# source_eagle.net
KiCad netlist of a schematic drawn in EAGLE
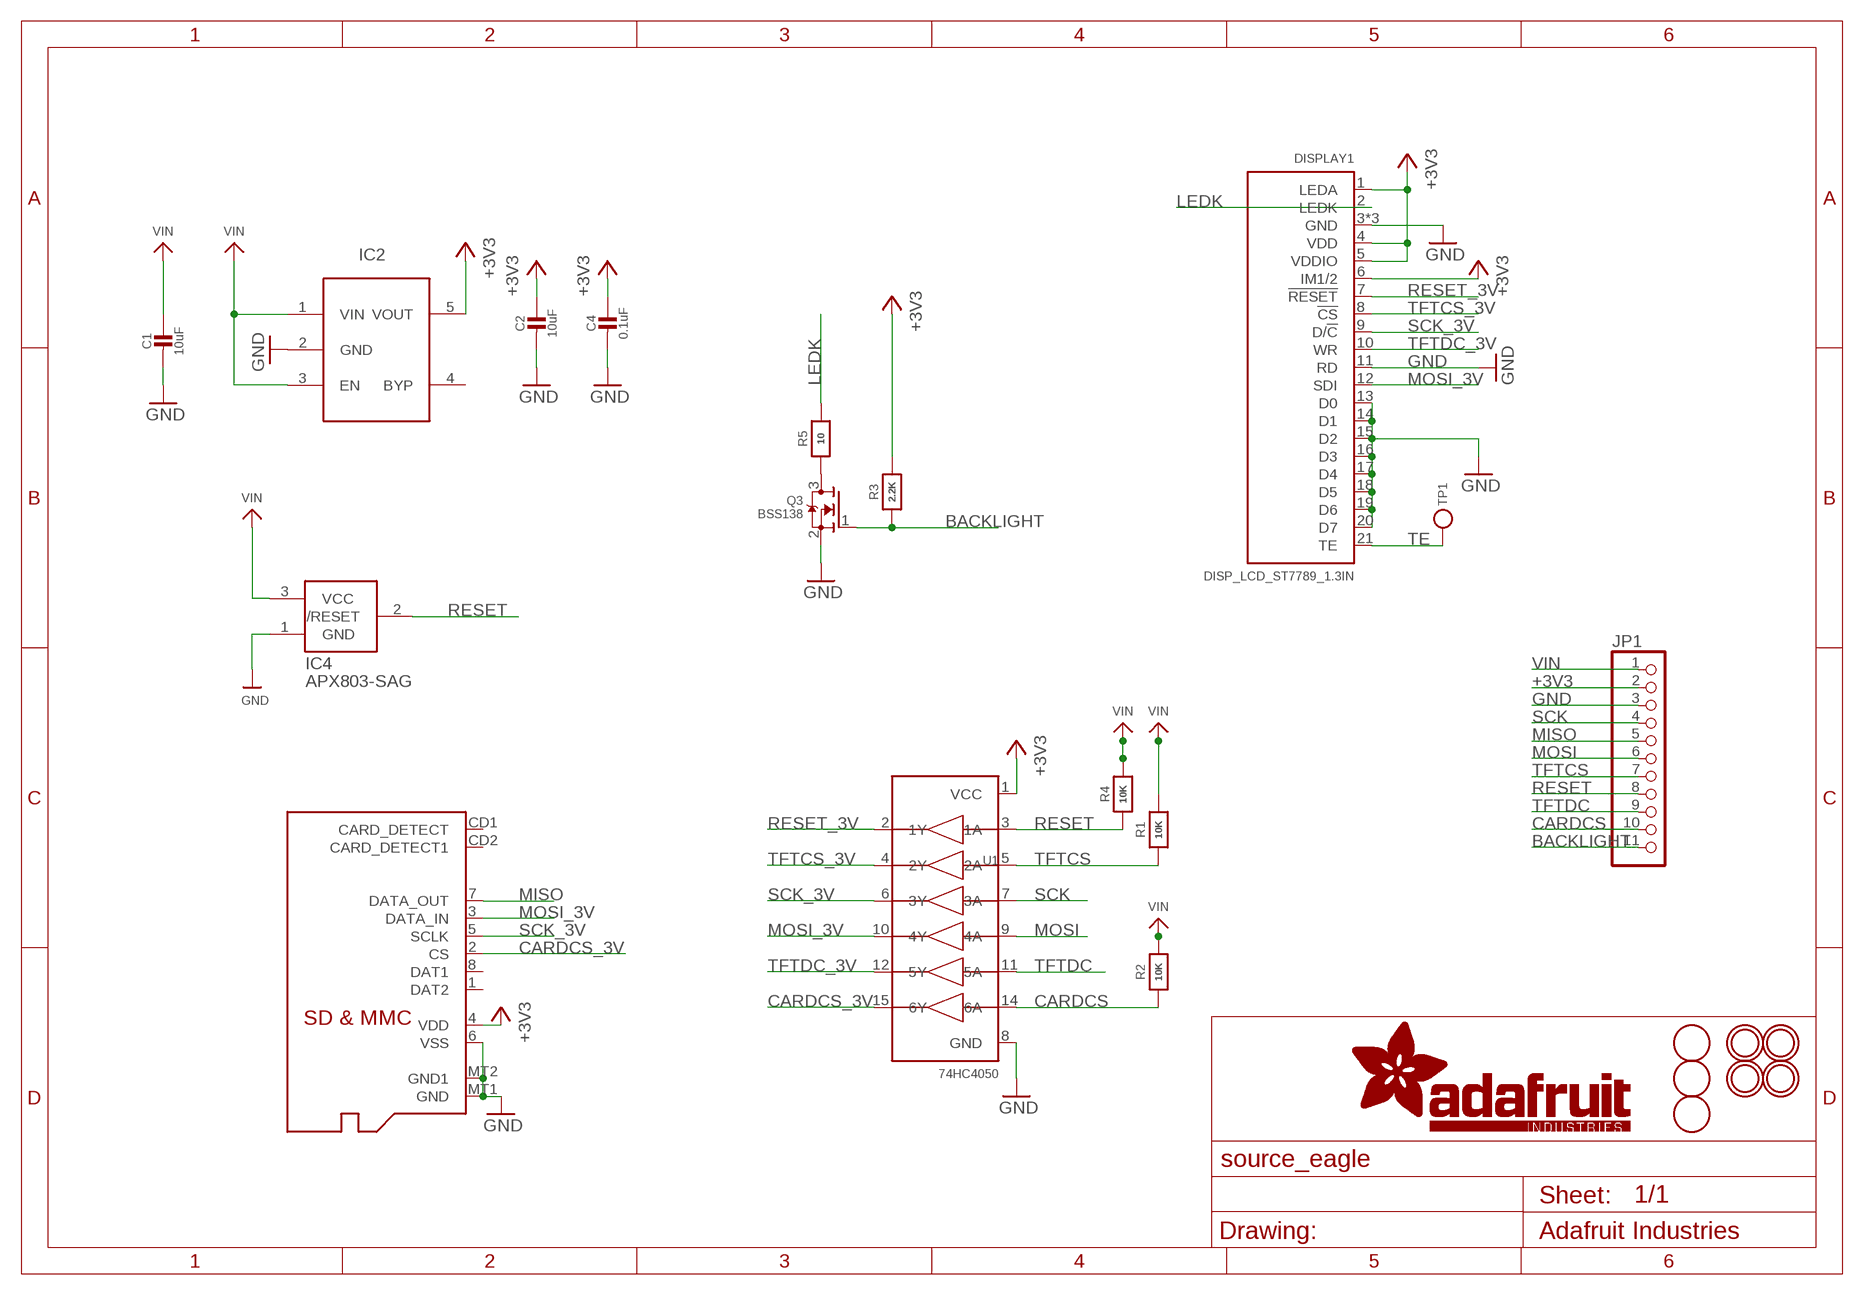
[diagram p0: schematic, sheet 1]

(export (version "E")
  (design (tool "Eeschema 10.0.6"))
  (components
    (comp (ref "C1")
      (value "10uF")
      (footprint "eagle-import:0805-NO")
      (libsource (lib "eagle-import") (part "CAP_CERAMIC0805-NOOUTLINE"))
    )
    (comp (ref "C2")
      (value "10uF")
      (footprint "eagle-import:0805-NO")
      (libsource (lib "eagle-import") (part "CAP_CERAMIC0805-NOOUTLINE"))
    )
    (comp (ref "C4")
      (value "0.1uF")
      (footprint "eagle-import:0603-NO")
      (libsource (lib "eagle-import") (part "CAP_CERAMIC0603_NO"))
    )
    (comp (ref "DISPLAY1")
      (value "DISP_LCD_ST7789_1.3IN")
      (footprint "eagle-import:TFT_1.3IN_240X240_24P")
      (libsource (lib "eagle-import") (part "DISP_LCD_ST7789_1.3IN"))
    )
    (comp (ref "IC2")
      (value "AP2112K-3.3")
      (footprint "eagle-import:SOT23-5L")
      (libsource (lib "eagle-import") (part "LP298XS"))
    )
    (comp (ref "IC4")
      (value "APX803-SAG")
      (footprint "eagle-import:SOT23")
      (libsource (lib "eagle-import") (part "AXP083-SAG"))
    )
    (comp (ref "JP1")
      (value "HEADER-1X1176MIL")
      (footprint "eagle-import:1X11_ROUND_76")
      (libsource (lib "eagle-import") (part "HEADER-1X1176MIL"))
    )
    (comp (ref "Q2")
      (value "MICROSD")
      (footprint "eagle-import:MICROSD")
      (libsource (lib "eagle-import") (part "MICROSD"))
    )
    (comp (ref "Q3")
      (value "BSS138")
      (footprint "eagle-import:SOT23-WIDE")
      (libsource (lib "eagle-import") (part "MOSFET-NWIDE"))
    )
    (comp (ref "R1")
      (value "10K")
      (footprint "eagle-import:0603-NO")
      (libsource (lib "eagle-import") (part "RESISTOR_0603_NOOUT"))
    )
    (comp (ref "R2")
      (value "10K")
      (footprint "eagle-import:0603-NO")
      (libsource (lib "eagle-import") (part "RESISTOR_0603_NOOUT"))
    )
    (comp (ref "R3")
      (value "2.2K")
      (footprint "eagle-import:0603-NO")
      (libsource (lib "eagle-import") (part "RESISTOR_0603_NOOUT"))
    )
    (comp (ref "R4")
      (value "10K")
      (footprint "eagle-import:0603-NO")
      (libsource (lib "eagle-import") (part "RESISTOR_0603_NOOUT"))
    )
    (comp (ref "R5")
      (value "10")
      (footprint "eagle-import:0603-NO")
      (libsource (lib "eagle-import") (part "RESISTOR_0603_NOOUT"))
    )
    (comp (ref "TP1")
      (value "TESTPOINTROUND1.5MM")
      (footprint "eagle-import:TESTPOINT_ROUND_1.5MM")
      (libsource (lib "eagle-import") (part "TESTPOINTROUND1.5MM"))
    )
    (comp (ref "U$3")
      (value "FIDUCIAL")
      (footprint "eagle-import:FIDUCIAL_1MM")
      (libsource (lib "eagle-import") (part "FIDUCIAL"))
    )
    (comp (ref "U$4")
      (value "FIDUCIAL")
      (footprint "eagle-import:FIDUCIAL_1MM")
      (libsource (lib "eagle-import") (part "FIDUCIAL"))
    )
    (comp (ref "U$5")
      (value "FIDUCIAL")
      (footprint "eagle-import:FIDUCIAL_1MM")
      (libsource (lib "eagle-import") (part "FIDUCIAL"))
    )
    (comp (ref "U$7")
      (value "MOUNTINGHOLE2.5")
      (footprint "eagle-import:MOUNTINGHOLE_2.5_PLATED")
      (libsource (lib "eagle-import") (part "MOUNTINGHOLE2.5"))
    )
    (comp (ref "U$8")
      (value "MOUNTINGHOLE2.5")
      (footprint "eagle-import:MOUNTINGHOLE_2.5_PLATED")
      (libsource (lib "eagle-import") (part "MOUNTINGHOLE2.5"))
    )
    (comp (ref "U$9")
      (value "MOUNTINGHOLE2.5")
      (footprint "eagle-import:MOUNTINGHOLE_2.5_PLATED")
      (libsource (lib "eagle-import") (part "MOUNTINGHOLE2.5"))
    )
    (comp (ref "U$10")
      (value "MOUNTINGHOLE2.5")
      (footprint "eagle-import:MOUNTINGHOLE_2.5_PLATED")
      (libsource (lib "eagle-import") (part "MOUNTINGHOLE2.5"))
    )
    (comp (ref "U1")
      (value "74HC4050")
      (footprint "eagle-import:TSSOP16")
      (libsource (lib "eagle-import") (part "74HC4050DTSSOP"))
    )
  )
  (nets
    (net (code "1") (name "+3V3") (class "Default")
      (node (ref "C2") (pin "1") (pinfunction "1_1") (pintype "passive"))
      (node (ref "C4") (pin "1") (pinfunction "1_1") (pintype "passive"))
      (node (ref "DISPLAY1") (pin "1") (pinfunction "LEDA_1") (pintype "input"))
      (node (ref "DISPLAY1") (pin "4") (pinfunction "VDD_4") (pintype "power_in"))
      (node (ref "DISPLAY1") (pin "5") (pinfunction "VDDIO_5") (pintype "power_in"))
      (node (ref "DISPLAY1") (pin "6") (pinfunction "IM1/2_6") (pintype "input"))
      (node (ref "IC2") (pin "5") (pinfunction "VOUT_5") (pintype "bidirectional"))
      (node (ref "JP1") (pin "2") (pinfunction "2_2") (pintype "passive"))
      (node (ref "Q2") (pin "4") (pinfunction "VDD_4") (pintype "power_in"))
      (node (ref "R3") (pin "2") (pinfunction "2_2") (pintype "passive"))
      (node (ref "U1") (pin "1") (pinfunction "VCC_1") (pintype "bidirectional"))
    )
    (net (code "2") (name "/BACKLIGHT") (class "Default")
      (node (ref "JP1") (pin "11") (pinfunction "11_11") (pintype "passive"))
      (node (ref "Q3") (pin "1") (pinfunction "G_1") (pintype "bidirectional"))
      (node (ref "R3") (pin "1") (pinfunction "1_1") (pintype "passive"))
    )
    (net (code "3") (name "/CARDCS") (class "Default")
      (node (ref "JP1") (pin "10") (pinfunction "10_10") (pintype "passive"))
      (node (ref "R2") (pin "1") (pinfunction "1_1") (pintype "passive"))
      (node (ref "U1") (pin "14") (pinfunction "6A_14") (pintype "bidirectional"))
    )
    (net (code "4") (name "/CARDCS_3V") (class "Default")
      (node (ref "Q2") (pin "2") (pinfunction "CS_2") (pintype "input"))
      (node (ref "U1") (pin "15") (pinfunction "6Y_15") (pintype "bidirectional"))
    )
    (net (code "5") (name "/LEDK") (class "Default")
      (node (ref "DISPLAY1") (pin "2") (pinfunction "LEDK_2") (pintype "input"))
      (node (ref "R5") (pin "2") (pinfunction "2_2") (pintype "passive"))
    )
    (net (code "6") (name "/MISO") (class "Default")
      (node (ref "JP1") (pin "5") (pinfunction "5_5") (pintype "passive"))
      (node (ref "Q2") (pin "7") (pinfunction "DATA_OUT_7") (pintype "output"))
    )
    (net (code "7") (name "/MOSI") (class "Default")
      (node (ref "JP1") (pin "6") (pinfunction "6_6") (pintype "passive"))
      (node (ref "U1") (pin "9") (pinfunction "4A_9") (pintype "bidirectional"))
    )
    (net (code "8") (name "/MOSI_3V") (class "Default")
      (node (ref "DISPLAY1") (pin "12") (pinfunction "SDI_12") (pintype "input"))
      (node (ref "Q2") (pin "3") (pinfunction "DATA_IN_3") (pintype "input"))
      (node (ref "U1") (pin "10") (pinfunction "4Y_10") (pintype "bidirectional"))
    )
    (net (code "9") (name "/RESET") (class "Default")
      (node (ref "IC4") (pin "2") (pinfunction "/RESET_2") (pintype "output"))
      (node (ref "JP1") (pin "8") (pinfunction "8_8") (pintype "passive"))
      (node (ref "R4") (pin "1") (pinfunction "1_1") (pintype "passive"))
      (node (ref "U1") (pin "3") (pinfunction "1A_3") (pintype "bidirectional"))
    )
    (net (code "10") (name "/RESET_3V") (class "Default")
      (node (ref "DISPLAY1") (pin "7") (pinfunction "~{RESET}_7") (pintype "input"))
      (node (ref "U1") (pin "2") (pinfunction "1Y_2") (pintype "bidirectional"))
    )
    (net (code "11") (name "/SCK") (class "Default")
      (node (ref "JP1") (pin "4") (pinfunction "4_4") (pintype "passive"))
      (node (ref "U1") (pin "7") (pinfunction "3A_7") (pintype "bidirectional"))
    )
    (net (code "12") (name "/SCK_3V") (class "Default")
      (node (ref "DISPLAY1") (pin "9") (pinfunction "D/~{C}_9") (pintype "input"))
      (node (ref "Q2") (pin "5") (pinfunction "SCLK_5") (pintype "input"))
      (node (ref "U1") (pin "6") (pinfunction "3Y_6") (pintype "bidirectional"))
    )
    (net (code "13") (name "/TE") (class "Default")
      (node (ref "DISPLAY1") (pin "21") (pinfunction "TE_21") (pintype "output"))
      (node (ref "TP1") (pin "P$1") (pinfunction "P$1_P$1") (pintype "bidirectional"))
    )
    (net (code "14") (name "/TFTCS") (class "Default")
      (node (ref "JP1") (pin "7") (pinfunction "7_7") (pintype "passive"))
      (node (ref "R1") (pin "1") (pinfunction "1_1") (pintype "passive"))
      (node (ref "U1") (pin "5") (pinfunction "2A_5") (pintype "bidirectional"))
    )
    (net (code "15") (name "/TFTCS_3V") (class "Default")
      (node (ref "DISPLAY1") (pin "8") (pinfunction "~{CS}_8") (pintype "input"))
      (node (ref "U1") (pin "4") (pinfunction "2Y_4") (pintype "bidirectional"))
    )
    (net (code "16") (name "/TFTDC") (class "Default")
      (node (ref "JP1") (pin "9") (pinfunction "9_9") (pintype "passive"))
      (node (ref "U1") (pin "11") (pinfunction "5A_11") (pintype "bidirectional"))
    )
    (net (code "17") (name "/TFTDC_3V") (class "Default")
      (node (ref "DISPLAY1") (pin "10") (pinfunction "WR_10") (pintype "input"))
      (node (ref "U1") (pin "12") (pinfunction "5Y_12") (pintype "bidirectional"))
    )
    (net (code "18") (name "GND") (class "Default")
      (node (ref "C1") (pin "2") (pinfunction "2_2") (pintype "passive"))
      (node (ref "C2") (pin "2") (pinfunction "2_2") (pintype "passive"))
      (node (ref "C4") (pin "2") (pinfunction "2_2") (pintype "passive"))
      (node (ref "DISPLAY1") (pin "11") (pinfunction "RD_11") (pintype "input"))
      (node (ref "DISPLAY1") (pin "13") (pinfunction "D0_13") (pintype "bidirectional"))
      (node (ref "DISPLAY1") (pin "14") (pinfunction "D1_14") (pintype "bidirectional"))
      (node (ref "DISPLAY1") (pin "15") (pinfunction "D2_15") (pintype "bidirectional"))
      (node (ref "DISPLAY1") (pin "16") (pinfunction "D3_16") (pintype "bidirectional"))
      (node (ref "DISPLAY1") (pin "17") (pinfunction "D4_17") (pintype "bidirectional"))
      (node (ref "DISPLAY1") (pin "18") (pinfunction "D5_18") (pintype "bidirectional"))
      (node (ref "DISPLAY1") (pin "19") (pinfunction "D6_19") (pintype "bidirectional"))
      (node (ref "DISPLAY1") (pin "20") (pinfunction "D7_20") (pintype "bidirectional"))
      (node (ref "DISPLAY1") (pin "23") (pinfunction "GND_23") (pintype "power_in"))
      (node (ref "DISPLAY1") (pin "24") (pinfunction "GND_24") (pintype "power_in"))
      (node (ref "DISPLAY1") (pin "3") (pinfunction "GND_3") (pintype "power_in"))
      (node (ref "IC2") (pin "2") (pinfunction "GND_2") (pintype "bidirectional"))
      (node (ref "IC4") (pin "1") (pinfunction "GND_1") (pintype "power_in"))
      (node (ref "JP1") (pin "3") (pinfunction "3_3") (pintype "passive"))
      (node (ref "Q2") (pin "6") (pinfunction "VSS_6") (pintype "power_in"))
      (node (ref "Q2") (pin "MT1") (pinfunction "GND_MT1") (pintype "power_in"))
      (node (ref "Q2") (pin "MT2") (pinfunction "GND1_MT2") (pintype "power_in"))
      (node (ref "Q3") (pin "2") (pinfunction "S_2") (pintype "bidirectional"))
      (node (ref "U1") (pin "8") (pinfunction "GND_8") (pintype "bidirectional"))
    )
    (net (code "19") (name "Net-(Q3-D)") (class "Default")
      (node (ref "Q3") (pin "3") (pinfunction "D_3") (pintype "bidirectional"))
      (node (ref "R5") (pin "1") (pinfunction "1_1") (pintype "passive"))
    )
    (net (code "20") (name "VIN") (class "Default")
      (node (ref "C1") (pin "1") (pinfunction "1_1") (pintype "passive"))
      (node (ref "IC2") (pin "1") (pinfunction "VIN_1") (pintype "bidirectional"))
      (node (ref "IC2") (pin "3") (pinfunction "EN_3") (pintype "bidirectional"))
      (node (ref "IC4") (pin "3") (pinfunction "VCC_3") (pintype "power_in"))
      (node (ref "JP1") (pin "1") (pinfunction "1_1") (pintype "passive"))
      (node (ref "R1") (pin "2") (pinfunction "2_2") (pintype "passive"))
      (node (ref "R2") (pin "2") (pinfunction "2_2") (pintype "passive"))
      (node (ref "R4") (pin "2") (pinfunction "2_2") (pintype "passive"))
    )
    (net (code "21") (name "unconnected-(IC2-BYP-Pad4)") (class "Default")
      (node (ref "IC2") (pin "4") (pinfunction "BYP_4") (pintype "bidirectional"))
    )
    (net (code "22") (name "unconnected-(Q2-CARD_DETECT-PadCD1)") (class "Default")
      (node (ref "Q2") (pin "CD1") (pinfunction "CARD_DETECT_CD1") (pintype "passive"))
    )
    (net (code "23") (name "unconnected-(Q2-CARD_DETECT1-PadCD2)") (class "Default")
      (node (ref "Q2") (pin "CD2") (pinfunction "CARD_DETECT1_CD2") (pintype "passive"))
    )
    (net (code "24") (name "unconnected-(Q2-DAT1-Pad8)") (class "Default")
      (node (ref "Q2") (pin "8") (pinfunction "DAT1_8") (pintype "bidirectional"))
    )
    (net (code "25") (name "unconnected-(Q2-DAT2-Pad1)") (class "Default")
      (node (ref "Q2") (pin "1") (pinfunction "DAT2_1") (pintype "bidirectional"))
    )
  )
)
